# 447Power.net
KiCad netlist of a schematic drawn in Altium Designer
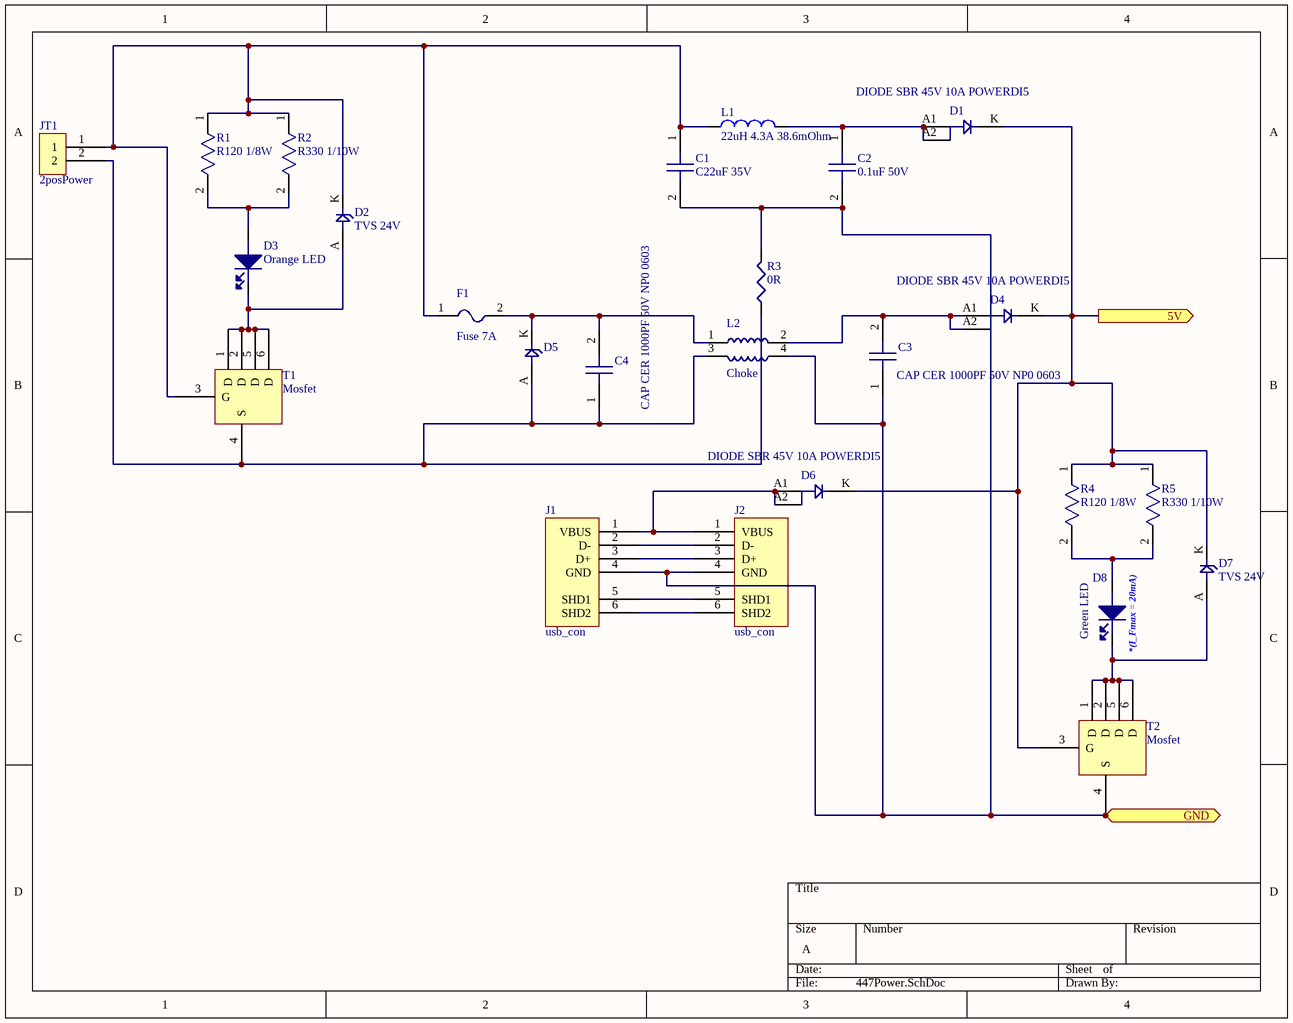
[diagram p0: 447Power.SchDoc]

(export (version "E")
  (design (tool "Eeschema 10.0.6"))
  (components
    (comp (ref "C1")
      (value "C22uF 35V")
      (footprint "C0603")
      (description "CAP CER 22UF 35V X5R 1206")
      (fields
        (field (name "MANUFACTURER") "TDK Corporation")
        (field (name "MANUFACTURER PART NUMBER") "C3216X5R1V226M160AC")
      )
      (libsource (lib "Schlib1") (part "C3216X5R1V226M160AC"))
    )
    (comp (ref "C2")
      (value "0.1uF 50V")
      (footprint "C0603")
      (description "CAP CER 0.1UF 50V X7R 0603")
      (fields
        (field (name "MANUFACTURER") "Yageo")
        (field (name "MANUFACTURER PART NUMBER") "CC0603KRX7R9BB104")
      )
      (libsource (lib "Schlib1") (part "CC0603KRX7R9BB104"))
    )
    (comp (ref "C3")
      (value "CAP CER 1000PF 50V NP0 0603")
      (footprint "C0603")
      (fields
        (field (name "MANUFACTURER") "Murata Electronics North America")
        (field (name "MANUFACTURER PART NUMBER") "GRM1885C1H102FA01J")
        (field (name "TOLERANCE") "±1%")
      )
      (libsource (lib "Schlib1") (part "GRM1885C1H102FA01J"))
    )
    (comp (ref "C4")
      (value "CAP CER 1000PF 50V NP0 0603")
      (footprint "C0603")
      (fields
        (field (name "MANUFACTURER") "Murata Electronics North America")
        (field (name "MANUFACTURER PART NUMBER") "GRM1885C1H102FA01J")
        (field (name "TOLERANCE") "±1%")
      )
      (libsource (lib "Schlib1") (part "GRM1885C1H102FA01J"))
    )
    (comp (ref "D1")
      (value "DIODE SBR 45V 10A POWERDI5")
      (footprint "Diode-Rect - 3D")
      (fields
        (field (name "MANUFACTURER") "Diodes Incorporated")
        (field (name "MANUFACTURER PART NUMBER") "SBR10U45SP5-13")
      )
      (libsource (lib "Schlib1") (part "SBR10U45SP5-13"))
    )
    (comp (ref "D2")
      (value "TVS 24V")
      (footprint "DO219AB_3DBody")
      (description "TVS DIODE 24VWM 38.9VC SMF")
      (fields
        (field (name "MANUFACTURER") "Vishay Semiconductor Diodes Division")
        (field (name "MANUFACTURER PART NUMBER") "SMF24A-E3-08")
      )
      (libsource (lib "Schlib1") (part "SMF24A-E3-08"))
    )
    (comp (ref "D3")
      (value "Orange LED")
      (footprint "LED_0603")
      (description "LED ORANGE DIFFUSED 0603 SMD")
      (fields
        (field (name "MANUFACTURER") "OSRAM Opto Semiconductors Inc.")
        (field (name "MANUFACTURER PART NUMBER") "LO L29K-H2K1-24-Z")
      )
      (libsource (lib "Schlib1") (part "LO L29K-H2K1-24-Z"))
    )
    (comp (ref "D4")
      (value "DIODE SBR 45V 10A POWERDI5")
      (footprint "Diode-Rect - 3D")
      (fields
        (field (name "MANUFACTURER") "Diodes Incorporated")
        (field (name "MANUFACTURER PART NUMBER") "SBR10U45SP5-13")
      )
      (libsource (lib "Schlib1") (part "SBR10U45SP5-13"))
    )
    (comp (ref "D5")
      (value "TVS DIODE 33VWM 53.3VC SMC")
      (footprint "SMC-TVS-33")
      (fields
        (field (name "MANUFACTURER") "Diodes Incorporated")
        (field (name "MANUFACTURER PART NUMBER") "SMCJ33CA-13-F")
      )
      (libsource (lib "Schlib1") (part "SMCJ33CA-13-F"))
    )
    (comp (ref "D6")
      (value "DIODE SBR 45V 10A POWERDI5")
      (footprint "Diode-Rect - 3D")
      (fields
        (field (name "MANUFACTURER") "Diodes Incorporated")
        (field (name "MANUFACTURER PART NUMBER") "SBR10U45SP5-13")
      )
      (libsource (lib "Schlib1") (part "SBR10U45SP5-13"))
    )
    (comp (ref "D7")
      (value "TVS 24V")
      (footprint "DO219AB_3DBody")
      (description "TVS DIODE 24VWM 38.9VC SMF")
      (fields
        (field (name "MANUFACTURER") "Vishay Semiconductor Diodes Division")
        (field (name "MANUFACTURER PART NUMBER") "SMF24A-E3-08")
      )
      (libsource (lib "Schlib1") (part "SMF24A-E3-08"))
    )
    (comp (ref "D8")
      (value "Green LED")
      (footprint "LED_0603")
      (description "LED GREEN DIFFUSED 0603 SMD")
      (fields
        (field (name "MANUFACTURER") "OSRAM Opto Semiconductors Inc.")
        (field (name "MANUFACTURER PART NUMBER") "LG L29K-G2J1-24-Z")
      )
      (libsource (lib "Schlib1") (part "LG L29K-G2J1-24-Z"))
    )
    (comp (ref "F1")
      (value "Fuse 7A")
      (footprint "Fuse")
      (description "FUSE 7.0A 125VAC FAST 1206")
      (fields (field (name "MANUFACTURER") "Bel Fuse Inc.") (field (name "MANUFACTURER PART NUMBER") "C1F 7"))
      (libsource (lib "Schlib1") (part "C1F 7"))
    )
    (comp (ref "J1")
      (value "usb_con")
      (footprint "USB_typeA")
      (description "CONN RCPT USB TYPE A R/A GOLD")
      (fields
        (field (name "MANUFACTURER") "Amphenol Commercial Products")
        (field (name "MANUFACTURER PART NUMBER") "UE27AC54100")
      )
      (libsource (lib "Schlib1") (part "UE27AC54100"))
    )
    (comp (ref "J2")
      (value "usb_con")
      (footprint "USB_typeA")
      (description "CONN RCPT USB TYPE A R/A GOLD")
      (fields
        (field (name "MANUFACTURER") "Amphenol Commercial Products")
        (field (name "MANUFACTURER PART NUMBER") "UE27AC54100")
      )
      (libsource (lib "") (part "UE27AC54100_1"))
    )
    (comp (ref "JT1")
      (value "2posPower")
      (footprint "GI TE con")
      (description "GIC6.0MM CONNECTOR HEADER 2POS")
      (fields
        (field (name "MANUFACTURER") "TE Connectivity AMP Connectors")
        (field (name "MANUFACTURER PART NUMBER") "2-2232876-1")
      )
      (libsource (lib "Schlib1") (part "2-2232876-1"))
    )
    (comp (ref "L1")
      (value "22uH 4.3A 38.6mOhm")
      (footprint "Inductor SRR1280A-220M - Original3D")
      (description "FIXED IND 22UH 4.3A 38.6 mOHM")
      (fields
        (field (name "MANUFACTURER") "Bourns Inc.")
        (field (name "MANUFACTURER PART NUMBER") "SRR1280A-220M")
      )
      (libsource (lib "Schlib1") (part "SRR1280A-220M"))
    )
    (comp (ref "L2")
      (value "Choke")
      (footprint "2744045447_SOJ254P850X305-4M")
      (description "FAIR-RITE - 2744045447 - FERRITE BEAD, 1400UOHM, 5A")
      (fields
        (field (name "MANUFACTURER") "FAIR-RITE")
        (field (name "MANUFACTURER PART NUMBER") "2744045447")
      )
      (libsource (lib "Schlib1") (part "2744045447"))
    )
    (comp (ref "R1")
      (value "R120 1/8W")
      (footprint "R0805")
      (description "RES SMD 120 OHM 1% 1/8W 0805")
      (fields
        (field (name "MANUFACTURER") "Yageo")
        (field (name "MANUFACTURER PART NUMBER") "RC0805FR-07120RL")
      )
      (libsource (lib "Schlib1") (part "RC0805FR-07120RL"))
    )
    (comp (ref "R2")
      (value "R330 1/10W")
      (footprint "R0603")
      (description "RES SMD 330 OHM 1% 1/10W 0603")
      (fields
        (field (name "MANUFACTURER") "Yageo")
        (field (name "MANUFACTURER PART NUMBER") "RC0603FR-07330RL")
      )
      (libsource (lib "Schlib1") (part "RC0603FR-07330RL"))
    )
    (comp (ref "R3")
      (value "0R")
      (footprint "R0805")
      (description "RES SMD 0.0 OHM JUMPER 1/8W 0805")
      (fields
        (field (name "MANUFACTURER") "Yageo")
        (field (name "MANUFACTURER PART NUMBER") "RC0805JR-070RL")
      )
      (libsource (lib "Schlib1") (part "RC0805JR-070RL_1"))
    )
    (comp (ref "R4")
      (value "R120 1/8W")
      (footprint "R0805")
      (description "RES SMD 120 OHM 1% 1/8W 0805")
      (fields
        (field (name "MANUFACTURER") "Yageo")
        (field (name "MANUFACTURER PART NUMBER") "RC0805FR-07120RL")
      )
      (libsource (lib "Schlib1") (part "RC0805FR-07120RL"))
    )
    (comp (ref "R5")
      (value "R330 1/10W")
      (footprint "R0603")
      (description "RES SMD 330 OHM 1% 1/10W 0603")
      (fields
        (field (name "MANUFACTURER") "Yageo")
        (field (name "MANUFACTURER PART NUMBER") "RC0603FR-07330RL")
      )
      (libsource (lib "Schlib1") (part "RC0603FR-07330RL"))
    )
    (comp (ref "T1")
      (value "Mosfet")
      (footprint "SOIC6-super")
      (description "MOSFET N-CH 30V 6.5A 6-SSOT")
      (fields
        (field (name "MANUFACTURER") "Fairchild Semiconductor")
        (field (name "MANUFACTURER PART NUMBER") "FDC8884")
      )
      (libsource (lib "Schlib1") (part "FDC8884"))
    )
    (comp (ref "T2")
      (value "Mosfet")
      (footprint "SOIC6-super")
      (description "MOSFET N-CH 30V 6.5A 6-SSOT")
      (fields
        (field (name "MANUFACTURER") "Fairchild Semiconductor")
        (field (name "MANUFACTURER PART NUMBER") "FDC8884")
      )
      (libsource (lib "Schlib1") (part "FDC8884"))
    )
  )
  (nets
    (net (code "1") (name "/5V") (class "Default")
      (node (ref "D1") (pin "K") (pinfunction "3_K") (pintype "passive"))
      (node (ref "D4") (pin "K") (pinfunction "3_K") (pintype "passive"))
      (node (ref "D6") (pin "K") (pinfunction "3_K") (pintype "passive"))
      (node (ref "D7") (pin "K") (pinfunction "2_K") (pintype "passive"))
      (node (ref "R4") (pin "1") (pinfunction "1_1") (pintype "passive"))
      (node (ref "R5") (pin "1") (pinfunction "1_1") (pintype "passive"))
      (node (ref "T2") (pin "3") (pinfunction "G_3") (pintype "passive"))
    )
    (net (code "2") (name "/GND") (class "Default")
      (node (ref "C1") (pin "2") (pinfunction "2_2") (pintype "passive"))
      (node (ref "C2") (pin "2") (pinfunction "2_2") (pintype "passive"))
      (node (ref "C3") (pin "1") (pinfunction "1_1") (pintype "passive"))
      (node (ref "J1") (pin "4") (pinfunction "GND_4") (pintype "passive"))
      (node (ref "J2") (pin "4") (pinfunction "GND_4") (pintype "passive"))
      (node (ref "L2") (pin "4") (pinfunction "4_4") (pintype "passive"))
      (node (ref "R3") (pin "2") (pinfunction "2_2") (pintype "passive"))
      (node (ref "T2") (pin "4") (pinfunction "S_4") (pintype "passive"))
    )
    (net (code "3") (name "Net-(D1-1)") (class "Default")
      (node (ref "C2") (pin "1") (pinfunction "1_1") (pintype "passive"))
      (node (ref "D1") (pin "A1") (pinfunction "1_A1") (pintype "passive"))
      (node (ref "D1") (pin "A2") (pinfunction "2_A2") (pintype "passive"))
      (node (ref "L1") (pin "2") (pinfunction "2_2") (pintype "passive"))
    )
    (net (code "4") (name "Net-(D2-1)") (class "Default")
      (node (ref "D2") (pin "A") (pinfunction "1_A") (pintype "passive"))
      (node (ref "D3") (pin "1") (pinfunction "Cathode_1") (pintype "passive"))
      (node (ref "T1") (pin "1") (pinfunction "D_1") (pintype "passive"))
      (node (ref "T1") (pin "2") (pinfunction "D_2") (pintype "passive"))
      (node (ref "T1") (pin "5") (pinfunction "D_5") (pintype "passive"))
      (node (ref "T1") (pin "6") (pinfunction "D_6") (pintype "passive"))
    )
    (net (code "5") (name "Net-(D2-2)") (class "Default")
      (node (ref "C1") (pin "1") (pinfunction "1_1") (pintype "passive"))
      (node (ref "D2") (pin "K") (pinfunction "2_K") (pintype "passive"))
      (node (ref "F1") (pin "1") (pinfunction "1_1") (pintype "passive"))
      (node (ref "JT1") (pin "1") (pinfunction "1_1") (pintype "passive"))
      (node (ref "L1") (pin "1") (pinfunction "1_1") (pintype "passive"))
      (node (ref "R1") (pin "1") (pinfunction "1_1") (pintype "passive"))
      (node (ref "R2") (pin "1") (pinfunction "1_1") (pintype "passive"))
      (node (ref "T1") (pin "3") (pinfunction "G_3") (pintype "passive"))
    )
    (net (code "6") (name "Net-(D3-Anode)") (class "Default")
      (node (ref "D3") (pin "2") (pinfunction "Anode_2") (pintype "passive"))
      (node (ref "R1") (pin "2") (pinfunction "2_2") (pintype "passive"))
      (node (ref "R2") (pin "2") (pinfunction "2_2") (pintype "passive"))
    )
    (net (code "7") (name "Net-(D4-1)") (class "Default")
      (node (ref "C3") (pin "2") (pinfunction "2_2") (pintype "passive"))
      (node (ref "D4") (pin "A1") (pinfunction "1_A1") (pintype "passive"))
      (node (ref "D4") (pin "A2") (pinfunction "2_A2") (pintype "passive"))
      (node (ref "L2") (pin "2") (pinfunction "2_2") (pintype "passive"))
    )
    (net (code "8") (name "Net-(D5-1)") (class "Default")
      (node (ref "C4") (pin "1") (pinfunction "1_1") (pintype "passive"))
      (node (ref "D5") (pin "A") (pinfunction "1_A") (pintype "passive"))
      (node (ref "JT1") (pin "2") (pinfunction "2_2") (pintype "passive"))
      (node (ref "L2") (pin "3") (pinfunction "3_3") (pintype "passive"))
      (node (ref "R3") (pin "1") (pinfunction "1_1") (pintype "passive"))
      (node (ref "T1") (pin "4") (pinfunction "S_4") (pintype "passive"))
    )
    (net (code "9") (name "Net-(D5-2)") (class "Default")
      (node (ref "C4") (pin "2") (pinfunction "2_2") (pintype "passive"))
      (node (ref "D5") (pin "K") (pinfunction "2_K") (pintype "passive"))
      (node (ref "F1") (pin "2") (pinfunction "2_2") (pintype "passive"))
      (node (ref "L2") (pin "1") (pinfunction "1_1") (pintype "passive"))
    )
    (net (code "10") (name "Net-(D6-1)") (class "Default")
      (node (ref "D6") (pin "A1") (pinfunction "1_A1") (pintype "passive"))
      (node (ref "D6") (pin "A2") (pinfunction "2_A2") (pintype "passive"))
      (node (ref "J1") (pin "1") (pinfunction "VBUS_1") (pintype "passive"))
      (node (ref "J2") (pin "1") (pinfunction "VBUS_1") (pintype "passive"))
    )
    (net (code "11") (name "Net-(D7-1)") (class "Default")
      (node (ref "D7") (pin "A") (pinfunction "1_A") (pintype "passive"))
      (node (ref "D8") (pin "1") (pinfunction "Cathode_1") (pintype "passive"))
      (node (ref "T2") (pin "1") (pinfunction "D_1") (pintype "passive"))
      (node (ref "T2") (pin "2") (pinfunction "D_2") (pintype "passive"))
      (node (ref "T2") (pin "5") (pinfunction "D_5") (pintype "passive"))
      (node (ref "T2") (pin "6") (pinfunction "D_6") (pintype "passive"))
    )
    (net (code "12") (name "Net-(D8-Anode)") (class "Default")
      (node (ref "D8") (pin "2") (pinfunction "Anode_2") (pintype "passive"))
      (node (ref "R4") (pin "2") (pinfunction "2_2") (pintype "passive"))
      (node (ref "R5") (pin "2") (pinfunction "2_2") (pintype "passive"))
    )
    (net (code "13") (name "Net-(J1-D+)") (class "Default")
      (node (ref "J1") (pin "3") (pinfunction "D+_3") (pintype "passive"))
      (node (ref "J2") (pin "3") (pinfunction "D+_3") (pintype "passive"))
    )
    (net (code "14") (name "Net-(J1-D-)") (class "Default")
      (node (ref "J1") (pin "2") (pinfunction "D-_2") (pintype "passive"))
      (node (ref "J2") (pin "2") (pinfunction "D-_2") (pintype "passive"))
    )
    (net (code "15") (name "Net-(J1-SHD1)") (class "Default")
      (node (ref "J1") (pin "5") (pinfunction "SHD1_5") (pintype "passive"))
      (node (ref "J2") (pin "5") (pinfunction "SHD1_5") (pintype "passive"))
    )
    (net (code "16") (name "Net-(J1-SHD2)") (class "Default")
      (node (ref "J1") (pin "6") (pinfunction "SHD2_6") (pintype "passive"))
      (node (ref "J2") (pin "6") (pinfunction "SHD2_6") (pintype "passive"))
    )
  )
)
